# XBeeBoosterPack.net
KiCad netlist of a schematic drawn in EAGLE
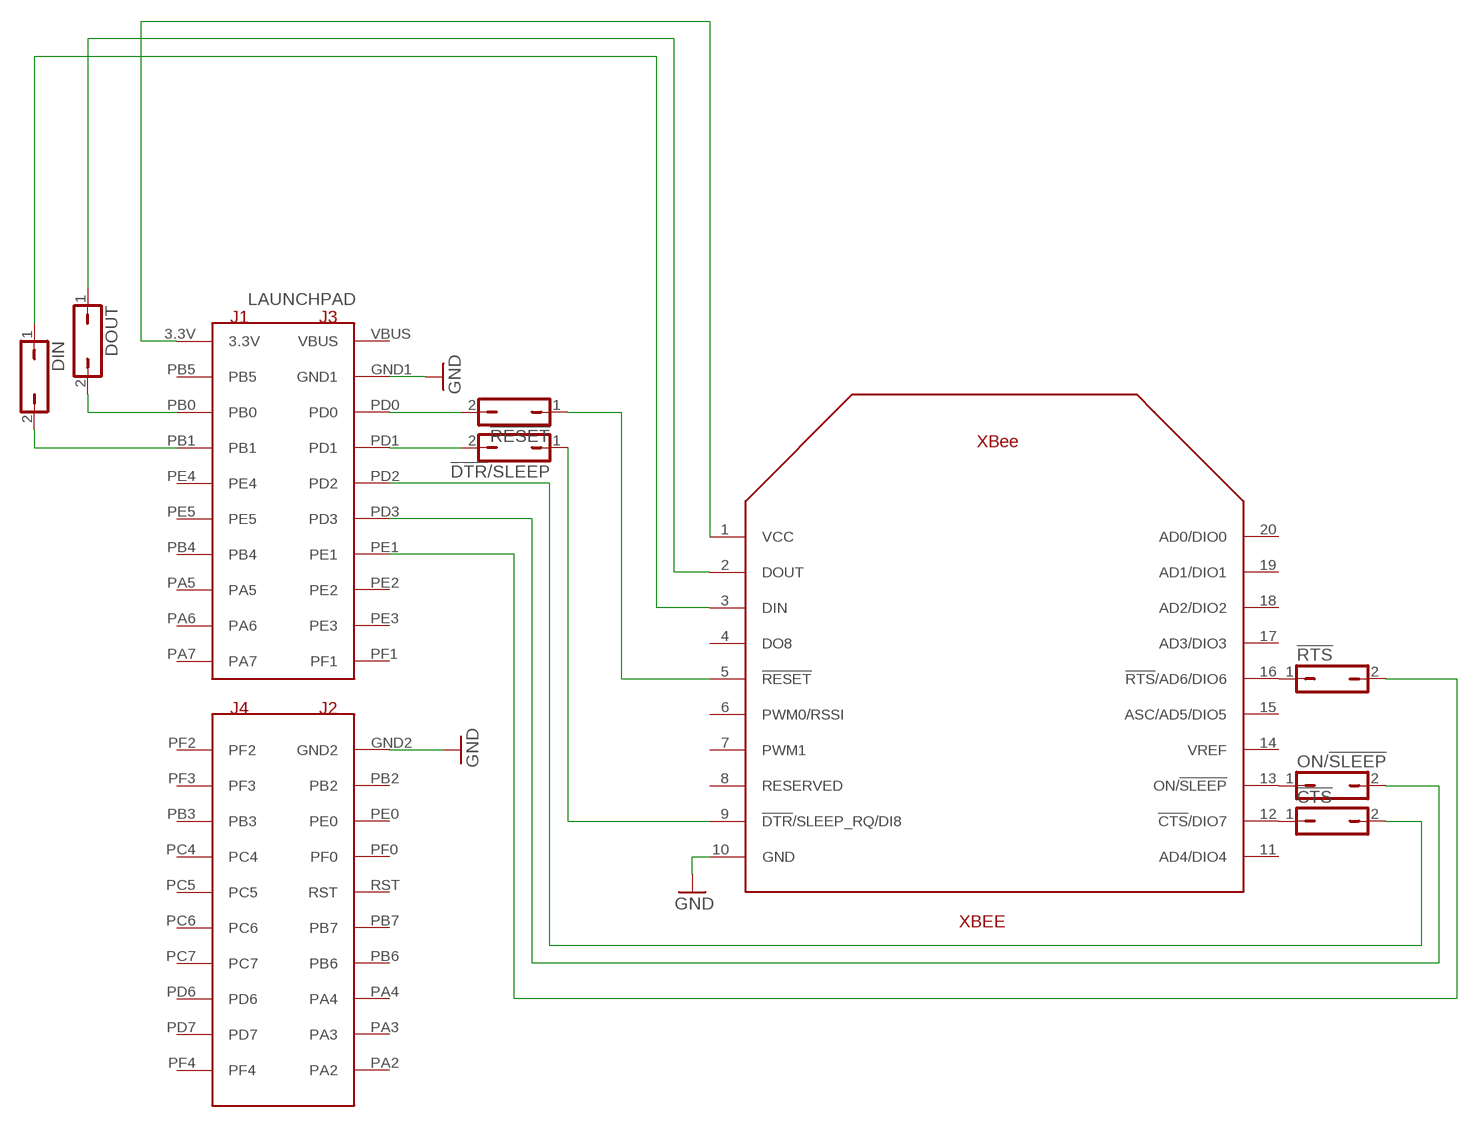
[diagram p0: schematic, sheet 1]

(export (version "E")
  (design (tool "Eeschema 10.0.6"))
  (components
    (comp (ref "!CTS!")
      (value "JP1Q")
      (footprint "eagle-import:JP1")
      (libsource (lib "eagle-import") (part "JP1Q"))
    )
    (comp (ref "!DTR!/SLEEP")
      (value "JP1Q")
      (footprint "eagle-import:JP1")
      (libsource (lib "eagle-import") (part "JP1Q"))
    )
    (comp (ref "!RESET")
      (value "JP1Q")
      (footprint "eagle-import:JP1")
      (libsource (lib "eagle-import") (part "JP1Q"))
    )
    (comp (ref "!RTS!")
      (value "JP1Q")
      (footprint "eagle-import:JP1")
      (libsource (lib "eagle-import") (part "JP1Q"))
    )
    (comp (ref "DIN")
      (value "JP1Q")
      (footprint "eagle-import:JP1")
      (libsource (lib "eagle-import") (part "JP1Q"))
    )
    (comp (ref "DOUT")
      (value "JP1Q")
      (footprint "eagle-import:JP1")
      (libsource (lib "eagle-import") (part "JP1Q"))
    )
    (comp (ref "LAUNCHPAD")
      (value "STELLARIS_LAUNCHPAD_BLIZZARD_XL_HEADERS")
      (footprint "eagle-import:STELLARISLAUNCHPADHEADERS")
      (libsource (lib "eagle-import") (part "STELLARIS_LAUNCHPAD_BLIZZARD_XL_HEADERS"))
    )
    (comp (ref "ON/!SLEEP!")
      (value "JP1Q")
      (footprint "eagle-import:JP1")
      (libsource (lib "eagle-import") (part "JP1Q"))
    )
    (comp (ref "XBEE")
      (value "XBEE_HEADERS")
      (footprint "eagle-import:XBEE_HEADERS")
      (libsource (lib "eagle-import") (part "XBEE_HEADERS"))
    )
  )
  (nets
    (net (code "1") (name "/RST") (class "Default")
      (node (ref "LAUNCHPAD") (pin "RST") (pinfunction "RST_RST") (pintype "power_in"))
    )
    (net (code "2") (name "/VBUS") (class "Default")
      (node (ref "LAUNCHPAD") (pin "VBUS") (pinfunction "VBUS_VBUS") (pintype "power_in"))
    )
    (net (code "3") (name "GND") (class "Default")
      (node (ref "LAUNCHPAD") (pin "GND1") (pinfunction "GND1_GND1") (pintype "bidirectional"))
      (node (ref "LAUNCHPAD") (pin "GND2") (pinfunction "GND2_GND2") (pintype "power_in"))
      (node (ref "XBEE") (pin "10") (pinfunction "GND_10") (pintype "bidirectional"))
    )
    (net (code "4") (name "Net-(!CTS!-Pad2)") (class "Default")
      (node (ref "!CTS!") (pin "2") (pinfunction "2_2") (pintype "passive"))
      (node (ref "LAUNCHPAD") (pin "PD2") (pinfunction "PD2_PD2") (pintype "bidirectional"))
    )
    (net (code "5") (name "Net-(!DTR!/SLEEP-Pad2)") (class "Default")
      (node (ref "!DTR!/SLEEP") (pin "2") (pinfunction "2_2") (pintype "passive"))
      (node (ref "LAUNCHPAD") (pin "PD1") (pinfunction "PD1_PD1") (pintype "bidirectional"))
    )
    (net (code "6") (name "Net-(!RESET-Pad2)") (class "Default")
      (node (ref "!RESET") (pin "2") (pinfunction "2_2") (pintype "passive"))
      (node (ref "LAUNCHPAD") (pin "PD0") (pinfunction "PD0_PD0") (pintype "bidirectional"))
    )
    (net (code "7") (name "Net-(!RTS!-Pad2)") (class "Default")
      (node (ref "!RTS!") (pin "2") (pinfunction "2_2") (pintype "passive"))
      (node (ref "LAUNCHPAD") (pin "PE1") (pinfunction "PE1_PE1") (pintype "bidirectional"))
    )
    (net (code "8") (name "Net-(DIN-Pad2)") (class "Default")
      (node (ref "DIN") (pin "2") (pinfunction "2_2") (pintype "passive"))
      (node (ref "LAUNCHPAD") (pin "PB1") (pinfunction "PB1_PB1") (pintype "bidirectional"))
    )
    (net (code "9") (name "Net-(DOUT-Pad2)") (class "Default")
      (node (ref "DOUT") (pin "2") (pinfunction "2_2") (pintype "passive"))
      (node (ref "LAUNCHPAD") (pin "PB0") (pinfunction "PB0_PB0") (pintype "bidirectional"))
    )
    (net (code "10") (name "Net-(LAUNCHPAD-PadPD3)") (class "Default")
      (node (ref "LAUNCHPAD") (pin "PD3") (pinfunction "PD3_PD3") (pintype "bidirectional"))
      (node (ref "ON/!SLEEP!") (pin "2") (pinfunction "2_2") (pintype "passive"))
    )
    (net (code "11") (name "Net-(XBEE-DIN)") (class "Default")
      (node (ref "DIN") (pin "1") (pinfunction "1_1") (pintype "passive"))
      (node (ref "XBEE") (pin "3") (pinfunction "DIN_3") (pintype "bidirectional"))
    )
    (net (code "12") (name "Net-(XBEE-DOUT)") (class "Default")
      (node (ref "DOUT") (pin "1") (pinfunction "1_1") (pintype "passive"))
      (node (ref "XBEE") (pin "2") (pinfunction "DOUT_2") (pintype "bidirectional"))
    )
    (net (code "13") (name "Net-(XBEE-ON{slash}~{SLEEP})") (class "Default")
      (node (ref "ON/!SLEEP!") (pin "1") (pinfunction "1_1") (pintype "passive"))
      (node (ref "XBEE") (pin "13") (pinfunction "ON/~{SLEEP}_13") (pintype "bidirectional"))
    )
    (net (code "14") (name "Net-(XBEE-VCC)") (class "Default")
      (node (ref "LAUNCHPAD") (pin "3.3V") (pinfunction "3.3V_3.3V") (pintype "power_in"))
      (node (ref "XBEE") (pin "1") (pinfunction "VCC_1") (pintype "bidirectional"))
    )
    (net (code "15") (name "Net-(XBEE-~{CTS}{slash}DIO7)") (class "Default")
      (node (ref "!CTS!") (pin "1") (pinfunction "1_1") (pintype "passive"))
      (node (ref "XBEE") (pin "12") (pinfunction "~{CTS}/DIO7_12") (pintype "bidirectional"))
    )
    (net (code "16") (name "Net-(XBEE-~{DTR}{slash}SLEEP_RQ{slash}DI8)") (class "Default")
      (node (ref "!DTR!/SLEEP") (pin "1") (pinfunction "1_1") (pintype "passive"))
      (node (ref "XBEE") (pin "9") (pinfunction "~{DTR}/SLEEP_RQ/DI8_9") (pintype "bidirectional"))
    )
    (net (code "17") (name "Net-(XBEE-~{RESET})") (class "Default")
      (node (ref "!RESET") (pin "1") (pinfunction "1_1") (pintype "passive"))
      (node (ref "XBEE") (pin "5") (pinfunction "~{RESET}_5") (pintype "bidirectional"))
    )
    (net (code "18") (name "Net-(XBEE-~{RTS}{slash}AD6{slash}DIO6)") (class "Default")
      (node (ref "!RTS!") (pin "1") (pinfunction "1_1") (pintype "passive"))
      (node (ref "XBEE") (pin "16") (pinfunction "~{RTS}/AD6/DIO6_16") (pintype "bidirectional"))
    )
    (net (code "19") (name "unconnected-(LAUNCHPAD-PadPA2)") (class "Default")
      (node (ref "LAUNCHPAD") (pin "PA2") (pinfunction "PA2_PA2") (pintype "bidirectional"))
    )
    (net (code "20") (name "unconnected-(LAUNCHPAD-PadPA3)") (class "Default")
      (node (ref "LAUNCHPAD") (pin "PA3") (pinfunction "PA3_PA3") (pintype "bidirectional"))
    )
    (net (code "21") (name "unconnected-(LAUNCHPAD-PadPA4)") (class "Default")
      (node (ref "LAUNCHPAD") (pin "PA4") (pinfunction "PA4_PA4") (pintype "bidirectional"))
    )
    (net (code "22") (name "unconnected-(LAUNCHPAD-PadPA5)") (class "Default")
      (node (ref "LAUNCHPAD") (pin "PA5") (pinfunction "PA5_PA5") (pintype "bidirectional"))
    )
    (net (code "23") (name "unconnected-(LAUNCHPAD-PadPA6)") (class "Default")
      (node (ref "LAUNCHPAD") (pin "PA6") (pinfunction "PA6_PA6") (pintype "bidirectional"))
    )
    (net (code "24") (name "unconnected-(LAUNCHPAD-PadPA7)") (class "Default")
      (node (ref "LAUNCHPAD") (pin "PA7") (pinfunction "PA7_PA7") (pintype "bidirectional"))
    )
    (net (code "25") (name "unconnected-(LAUNCHPAD-PadPB2)") (class "Default")
      (node (ref "LAUNCHPAD") (pin "PB2") (pinfunction "PB2_PB2") (pintype "bidirectional"))
    )
    (net (code "26") (name "unconnected-(LAUNCHPAD-PadPB3)") (class "Default")
      (node (ref "LAUNCHPAD") (pin "PB3") (pinfunction "PB3_PB3") (pintype "bidirectional"))
    )
    (net (code "27") (name "unconnected-(LAUNCHPAD-PadPB4)") (class "Default")
      (node (ref "LAUNCHPAD") (pin "PB4") (pinfunction "PB4_PB4") (pintype "bidirectional"))
    )
    (net (code "28") (name "unconnected-(LAUNCHPAD-PadPB5)") (class "Default")
      (node (ref "LAUNCHPAD") (pin "PB5") (pinfunction "PB5_PB5") (pintype "bidirectional"))
    )
    (net (code "29") (name "unconnected-(LAUNCHPAD-PadPB6)") (class "Default")
      (node (ref "LAUNCHPAD") (pin "PB6") (pinfunction "PB6_PB6") (pintype "bidirectional"))
    )
    (net (code "30") (name "unconnected-(LAUNCHPAD-PadPB7)") (class "Default")
      (node (ref "LAUNCHPAD") (pin "PB7") (pinfunction "PB7_PB7") (pintype "bidirectional"))
    )
    (net (code "31") (name "unconnected-(LAUNCHPAD-PadPC4)") (class "Default")
      (node (ref "LAUNCHPAD") (pin "PC4") (pinfunction "PC4_PC4") (pintype "bidirectional"))
    )
    (net (code "32") (name "unconnected-(LAUNCHPAD-PadPC5)") (class "Default")
      (node (ref "LAUNCHPAD") (pin "PC5") (pinfunction "PC5_PC5") (pintype "bidirectional"))
    )
    (net (code "33") (name "unconnected-(LAUNCHPAD-PadPC6)") (class "Default")
      (node (ref "LAUNCHPAD") (pin "PC6") (pinfunction "PC6_PC6") (pintype "bidirectional"))
    )
    (net (code "34") (name "unconnected-(LAUNCHPAD-PadPC7)") (class "Default")
      (node (ref "LAUNCHPAD") (pin "PC7") (pinfunction "PC7_PC7") (pintype "bidirectional"))
    )
    (net (code "35") (name "unconnected-(LAUNCHPAD-PadPD6)") (class "Default")
      (node (ref "LAUNCHPAD") (pin "PD6") (pinfunction "PD6_PD6") (pintype "bidirectional"))
    )
    (net (code "36") (name "unconnected-(LAUNCHPAD-PadPD7)") (class "Default")
      (node (ref "LAUNCHPAD") (pin "PD7") (pinfunction "PD7_PD7") (pintype "bidirectional"))
    )
    (net (code "37") (name "unconnected-(LAUNCHPAD-PadPE0)") (class "Default")
      (node (ref "LAUNCHPAD") (pin "PE0") (pinfunction "PE0_PE0") (pintype "bidirectional"))
    )
    (net (code "38") (name "unconnected-(LAUNCHPAD-PadPE2)") (class "Default")
      (node (ref "LAUNCHPAD") (pin "PE2") (pinfunction "PE2_PE2") (pintype "bidirectional"))
    )
    (net (code "39") (name "unconnected-(LAUNCHPAD-PadPE3)") (class "Default")
      (node (ref "LAUNCHPAD") (pin "PE3") (pinfunction "PE3_PE3") (pintype "bidirectional"))
    )
    (net (code "40") (name "unconnected-(LAUNCHPAD-PadPE4)") (class "Default")
      (node (ref "LAUNCHPAD") (pin "PE4") (pinfunction "PE4_PE4") (pintype "bidirectional"))
    )
    (net (code "41") (name "unconnected-(LAUNCHPAD-PadPE5)") (class "Default")
      (node (ref "LAUNCHPAD") (pin "PE5") (pinfunction "PE5_PE5") (pintype "bidirectional"))
    )
    (net (code "42") (name "unconnected-(LAUNCHPAD-PadPF0)") (class "Default")
      (node (ref "LAUNCHPAD") (pin "PF0") (pinfunction "PF0_PF0") (pintype "bidirectional"))
    )
    (net (code "43") (name "unconnected-(LAUNCHPAD-PadPF1)") (class "Default")
      (node (ref "LAUNCHPAD") (pin "PF1") (pinfunction "PF1_PF1") (pintype "bidirectional"))
    )
    (net (code "44") (name "unconnected-(LAUNCHPAD-PadPF2)") (class "Default")
      (node (ref "LAUNCHPAD") (pin "PF2") (pinfunction "PF2_PF2") (pintype "bidirectional"))
    )
    (net (code "45") (name "unconnected-(LAUNCHPAD-PadPF3)") (class "Default")
      (node (ref "LAUNCHPAD") (pin "PF3") (pinfunction "PF3_PF3") (pintype "bidirectional"))
    )
    (net (code "46") (name "unconnected-(LAUNCHPAD-PadPF4)") (class "Default")
      (node (ref "LAUNCHPAD") (pin "PF4") (pinfunction "PF4_PF4") (pintype "bidirectional"))
    )
    (net (code "47") (name "unconnected-(XBEE-AD0{slash}DIO0-Pad20)") (class "Default")
      (node (ref "XBEE") (pin "20") (pinfunction "AD0/DIO0_20") (pintype "bidirectional"))
    )
    (net (code "48") (name "unconnected-(XBEE-AD1{slash}DIO1-Pad19)") (class "Default")
      (node (ref "XBEE") (pin "19") (pinfunction "AD1/DIO1_19") (pintype "bidirectional"))
    )
    (net (code "49") (name "unconnected-(XBEE-AD2{slash}DIO2-Pad18)") (class "Default")
      (node (ref "XBEE") (pin "18") (pinfunction "AD2/DIO2_18") (pintype "bidirectional"))
    )
    (net (code "50") (name "unconnected-(XBEE-AD3{slash}DIO3-Pad17)") (class "Default")
      (node (ref "XBEE") (pin "17") (pinfunction "AD3/DIO3_17") (pintype "bidirectional"))
    )
    (net (code "51") (name "unconnected-(XBEE-AD4{slash}DIO4-Pad11)") (class "Default")
      (node (ref "XBEE") (pin "11") (pinfunction "AD4/DIO4_11") (pintype "bidirectional"))
    )
    (net (code "52") (name "unconnected-(XBEE-ASC{slash}AD5{slash}DIO5-Pad15)") (class "Default")
      (node (ref "XBEE") (pin "15") (pinfunction "ASC/AD5/DIO5_15") (pintype "bidirectional"))
    )
    (net (code "53") (name "unconnected-(XBEE-DO8-Pad4)") (class "Default")
      (node (ref "XBEE") (pin "4") (pinfunction "DO8_4") (pintype "bidirectional"))
    )
    (net (code "54") (name "unconnected-(XBEE-PWM0{slash}RSSI-Pad6)") (class "Default")
      (node (ref "XBEE") (pin "6") (pinfunction "PWM0/RSSI_6") (pintype "bidirectional"))
    )
    (net (code "55") (name "unconnected-(XBEE-PWM1-Pad7)") (class "Default")
      (node (ref "XBEE") (pin "7") (pinfunction "PWM1_7") (pintype "bidirectional"))
    )
    (net (code "56") (name "unconnected-(XBEE-RESERVED-Pad8)") (class "Default")
      (node (ref "XBEE") (pin "8") (pinfunction "RESERVED_8") (pintype "bidirectional"))
    )
    (net (code "57") (name "unconnected-(XBEE-VREF-Pad14)") (class "Default")
      (node (ref "XBEE") (pin "14") (pinfunction "VREF_14") (pintype "bidirectional"))
    )
  )
)
